# MyRIO_LickometerBreakout_Gamma1a.net
KiCad netlist of a schematic drawn in EAGLE
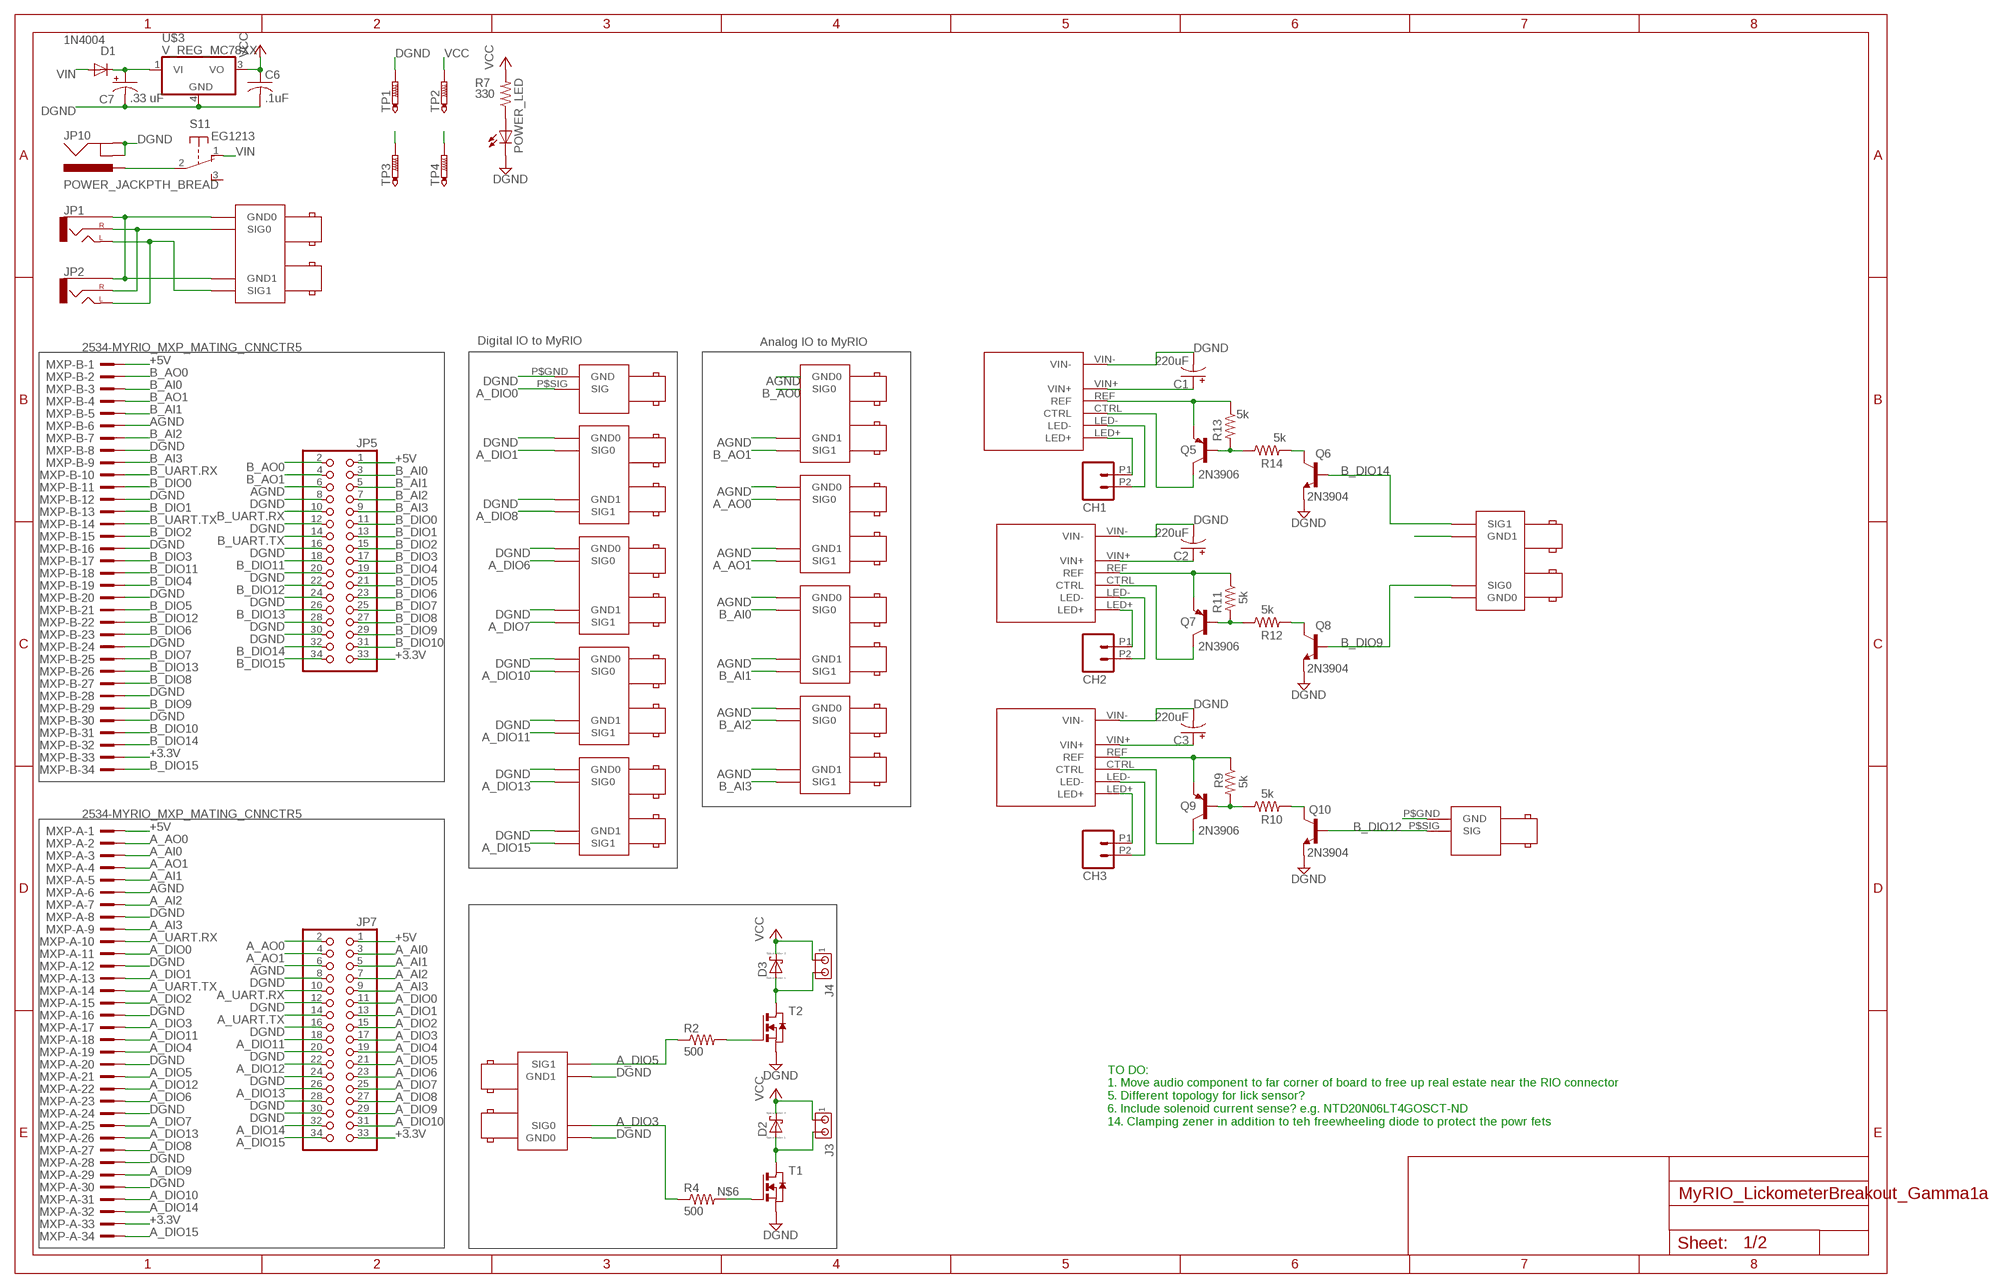
[diagram p0: schematic, sheet 1]
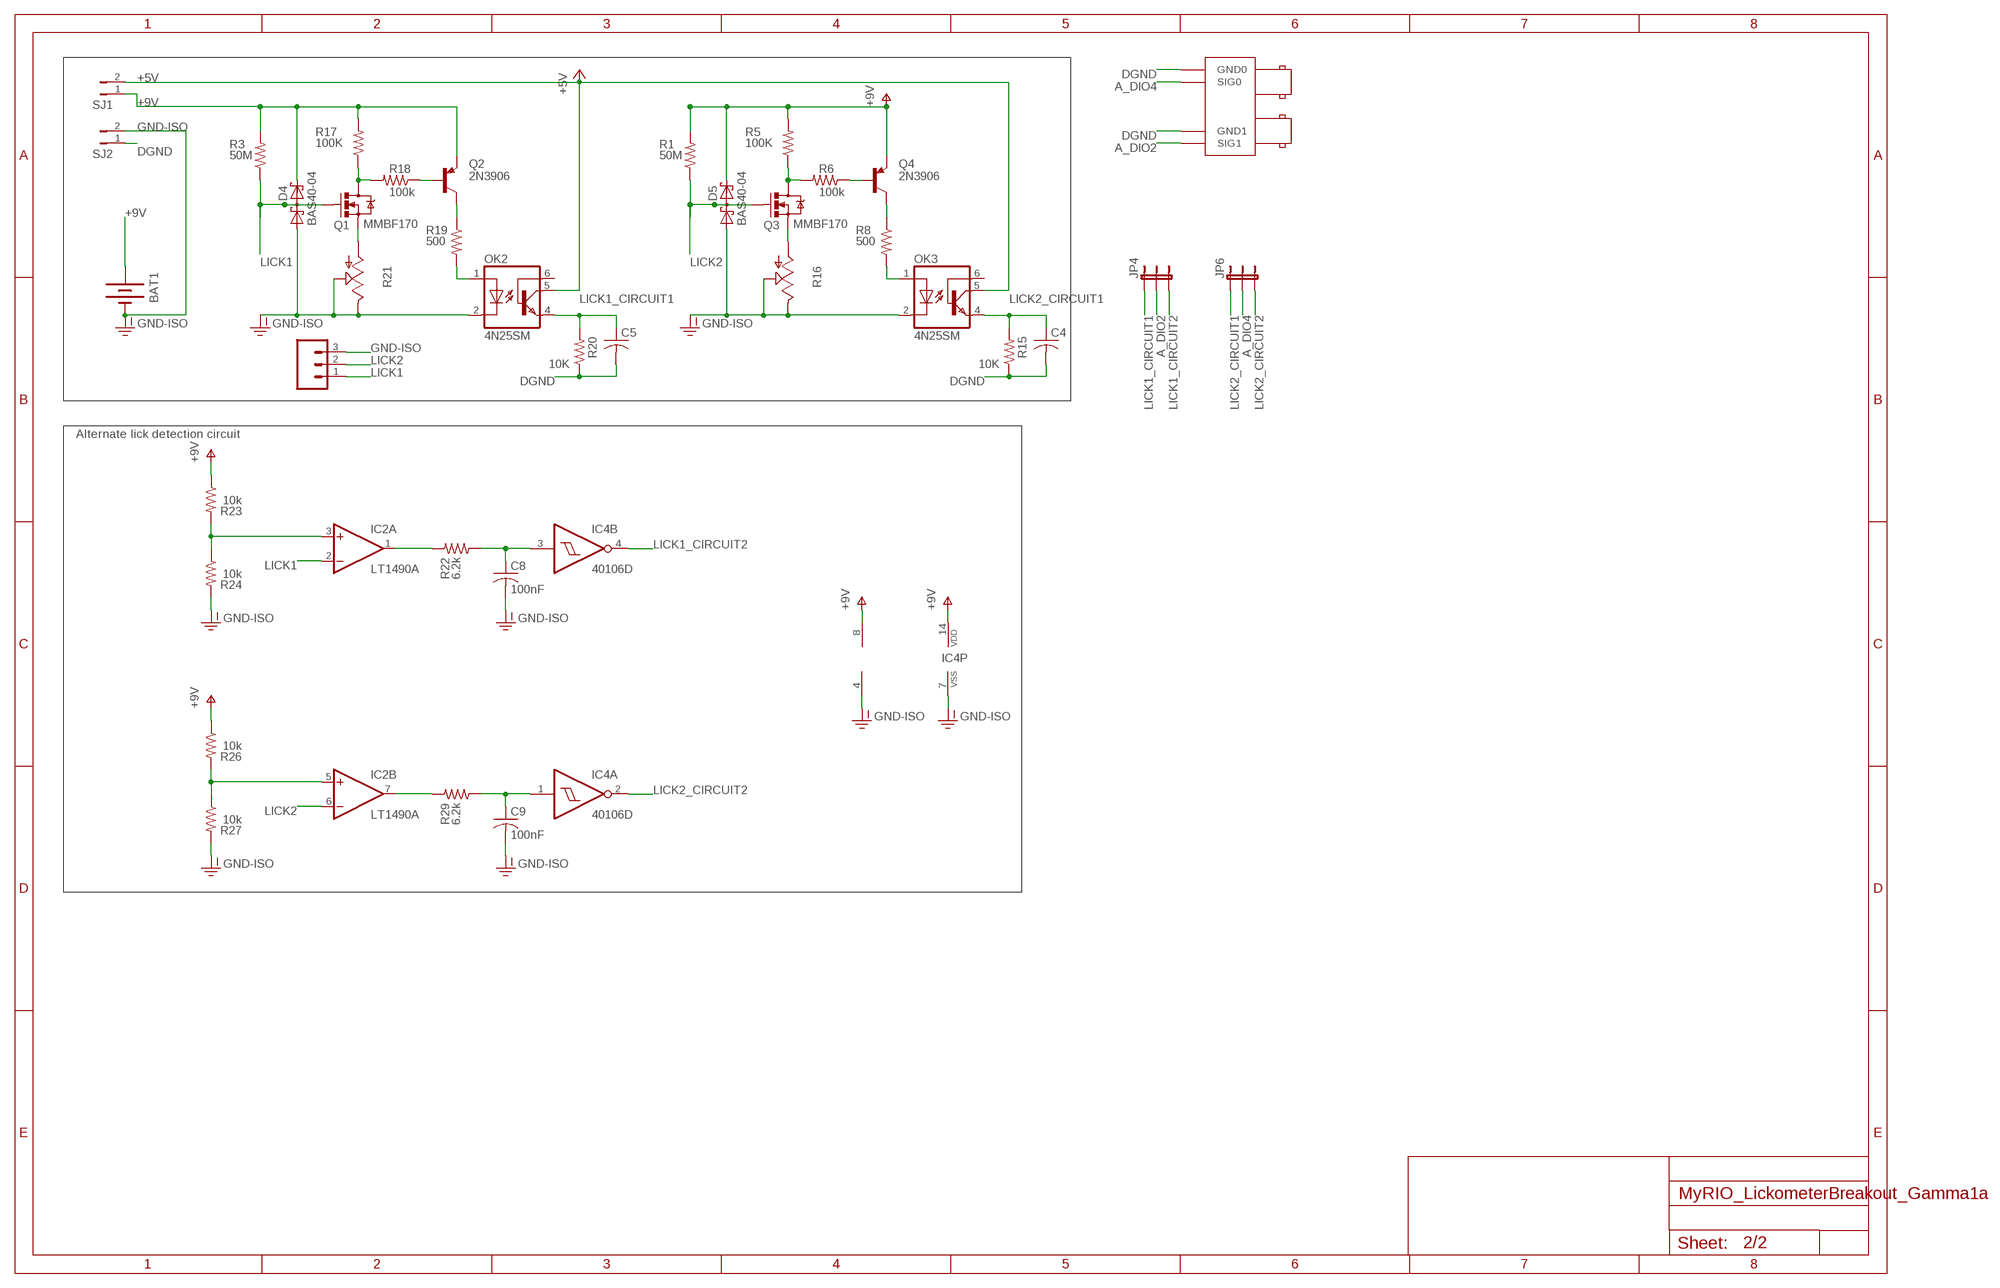
[diagram p1: schematic, sheet 2]

(export (version "E")
  (design (tool "Eeschema 10.0.6"))
  (components
    (comp (ref "BAT1")
      (value "BATTERY9V")
      (footprint "eagle-import:BATTCON_9V")
      (libsource (lib "eagle-import") (part "BATTERY9V"))
    )
    (comp (ref "C4")
      (value "C-US025-024X044")
      (footprint "eagle-import:C025-024X044")
      (libsource (lib "eagle-import") (part "C-US025-024X044"))
    )
    (comp (ref "C5")
      (value "C-US025-024X044")
      (footprint "eagle-import:C025-024X044")
      (libsource (lib "eagle-import") (part "C-US025-024X044"))
    )
    (comp (ref "C8")
      (value "100nF")
      (footprint "eagle-import:C0805")
      (libsource (lib "eagle-import") (part "C-USC0805"))
    )
    (comp (ref "C9")
      (value "100nF")
      (footprint "eagle-import:C0805")
      (libsource (lib "eagle-import") (part "C-USC0805"))
    )
    (comp (ref "D4")
      (value "BAS40-04")
      (footprint "eagle-import:SOT23")
      (libsource (lib "eagle-import") (part "BAS40-04"))
    )
    (comp (ref "D5")
      (value "BAS40-04")
      (footprint "eagle-import:SOT23")
      (libsource (lib "eagle-import") (part "BAS40-04"))
    )
    (comp (ref "IC2")
      (value "LT1490A")
      (footprint "eagle-import:SO08")
      (libsource (lib "eagle-import") (part "LM393D"))
    )
    (comp (ref "IC4")
      (value "40106D")
      (footprint "eagle-import:SO14")
      (libsource (lib "eagle-import") (part "40106D"))
    )
    (comp (ref "JP4")
      (value "JUMPER-3PTH")
      (footprint "eagle-import:1X03")
      (libsource (lib "eagle-import") (part "JUMPER-3PTH"))
    )
    (comp (ref "JP6")
      (value "JUMPER-3PTH")
      (footprint "eagle-import:1X03")
      (libsource (lib "eagle-import") (part "JUMPER-3PTH"))
    )
    (comp (ref "JP11")
      (value "M03POLAR")
      (footprint "eagle-import:MOLEX-1X3")
      (libsource (lib "eagle-import") (part "M03POLAR"))
    )
    (comp (ref "LICK")
      (value "BNC_RIGHT_ANGLE_DOUBLE")
      (footprint "eagle-import:BNC_RIGHT_ANGLE_DOUBLE")
      (libsource (lib "eagle-import") (part "BNC_RIGHT_ANGLE_DOUBLE"))
    )
    (comp (ref "OK2")
      (value "4N25SM")
      (footprint "eagle-import:DIL6-SMD")
      (fields (field (name "MF") "FAIRCHILD SEMICONDUCTOR"))
      (libsource (lib "eagle-import") (part "4N?MS25"))
    )
    (comp (ref "OK3")
      (value "4N25SM")
      (footprint "eagle-import:DIL6-SMD")
      (fields (field (name "MF") "FAIRCHILD SEMICONDUCTOR"))
      (libsource (lib "eagle-import") (part "4N?MS25"))
    )
    (comp (ref "Q1")
      (value "MMBF170")
      (footprint "eagle-import:SOT23-3")
      (libsource (lib "eagle-import") (part "MOSFET-NCHANNELAO3404A"))
    )
    (comp (ref "Q2")
      (value "2N3906")
      (footprint "eagle-import:SOT23-BEC")
      (libsource (lib "eagle-import") (part "-PNP-SOT23-BECMMBT3906LT1"))
    )
    (comp (ref "Q3")
      (value "MMBF170")
      (footprint "eagle-import:SOT23-3")
      (libsource (lib "eagle-import") (part "MOSFET-NCHANNELAO3404A"))
    )
    (comp (ref "Q4")
      (value "2N3906")
      (footprint "eagle-import:SOT23-BEC")
      (libsource (lib "eagle-import") (part "-PNP-SOT23-BECMMBT3906LT1"))
    )
    (comp (ref "R1")
      (value "50M")
      (footprint "eagle-import:0805S")
      (libsource (lib "eagle-import") (part "RESISTOR_SM0805S"))
    )
    (comp (ref "R3")
      (value "50M")
      (footprint "eagle-import:0805S")
      (libsource (lib "eagle-import") (part "RESISTOR_SM0805S"))
    )
    (comp (ref "R5")
      (value "100K")
      (footprint "eagle-import:0805S")
      (libsource (lib "eagle-import") (part "RESISTOR_SM0805S"))
    )
    (comp (ref "R6")
      (value "100k")
      (footprint "eagle-import:0805S")
      (libsource (lib "eagle-import") (part "RESISTOR_SM0805S"))
    )
    (comp (ref "R8")
      (value "500")
      (footprint "eagle-import:0805S")
      (libsource (lib "eagle-import") (part "RESISTOR_SM0805S"))
    )
    (comp (ref "R15")
      (value "10K")
      (footprint "eagle-import:0805S")
      (libsource (lib "eagle-import") (part "RESISTOR_SM0805S"))
    )
    (comp (ref "R16")
      (value "TRIM_US-B25P")
      (footprint "eagle-import:B25P")
      (libsource (lib "eagle-import") (part "TRIM_US-B25P"))
    )
    (comp (ref "R17")
      (value "100K")
      (footprint "eagle-import:0805S")
      (libsource (lib "eagle-import") (part "RESISTOR_SM0805S"))
    )
    (comp (ref "R18")
      (value "100k")
      (footprint "eagle-import:0805S")
      (libsource (lib "eagle-import") (part "RESISTOR_SM0805S"))
    )
    (comp (ref "R19")
      (value "500")
      (footprint "eagle-import:0805S")
      (libsource (lib "eagle-import") (part "RESISTOR_SM0805S"))
    )
    (comp (ref "R20")
      (value "10K")
      (footprint "eagle-import:0805S")
      (libsource (lib "eagle-import") (part "RESISTOR_SM0805S"))
    )
    (comp (ref "R21")
      (value "TRIM_US-B25P")
      (footprint "eagle-import:B25P")
      (libsource (lib "eagle-import") (part "TRIM_US-B25P"))
    )
    (comp (ref "R22")
      (value "6.2k")
      (footprint "eagle-import:0805S")
      (libsource (lib "eagle-import") (part "RESISTOR_SM0805S"))
    )
    (comp (ref "R23")
      (value "10k")
      (footprint "eagle-import:0805S")
      (libsource (lib "eagle-import") (part "RESISTOR_SM0805S"))
    )
    (comp (ref "R24")
      (value "10k")
      (footprint "eagle-import:0805S")
      (libsource (lib "eagle-import") (part "RESISTOR_SM0805S"))
    )
    (comp (ref "R26")
      (value "10k")
      (footprint "eagle-import:0805S")
      (libsource (lib "eagle-import") (part "RESISTOR_SM0805S"))
    )
    (comp (ref "R27")
      (value "10k")
      (footprint "eagle-import:0805S")
      (libsource (lib "eagle-import") (part "RESISTOR_SM0805S"))
    )
    (comp (ref "R29")
      (value "6.2k")
      (footprint "eagle-import:0805S")
      (libsource (lib "eagle-import") (part "RESISTOR_SM0805S"))
    )
    (comp (ref "SJ1")
      (value "JUMPER-PTH-2-NO")
      (footprint "eagle-import:PTH-JUMPER-2-NO_NO_SILK")
      (libsource (lib "eagle-import") (part "JUMPER-PTH-2-NO"))
    )
    (comp (ref "SJ2")
      (value "JUMPER-PTH-2-NO")
      (footprint "eagle-import:PTH-JUMPER-2-NO_NO_SILK")
      (libsource (lib "eagle-import") (part "JUMPER-PTH-2-NO"))
    )
    (comp (ref "AAO_0,1")
      (value "BNC_RIGHT_ANGLE_DOUBLE")
      (footprint "eagle-import:BNC_RIGHT_ANGLE_DOUBLE")
      (libsource (lib "eagle-import") (part "BNC_RIGHT_ANGLE_DOUBLE"))
    )
    (comp (ref "ACTV_REC")
      (value "BNC_RIGHT_ANGLE")
      (footprint "eagle-import:BNC_RIGHT_ANGLE")
      (libsource (lib "eagle-import") (part "BNC_RIGHT_ANGLE"))
    )
    (comp (ref "AUDIO")
      (value "BNC_RIGHT_ANGLE_DOUBLE")
      (footprint "eagle-import:BNC_RIGHT_ANGLE_DOUBLE")
      (libsource (lib "eagle-import") (part "BNC_RIGHT_ANGLE_DOUBLE"))
    )
    (comp (ref "BAI_0,1")
      (value "BNC_RIGHT_ANGLE_DOUBLE")
      (footprint "eagle-import:BNC_RIGHT_ANGLE_DOUBLE")
      (libsource (lib "eagle-import") (part "BNC_RIGHT_ANGLE_DOUBLE"))
    )
    (comp (ref "BAI_2,3")
      (value "BNC_RIGHT_ANGLE_DOUBLE")
      (footprint "eagle-import:BNC_RIGHT_ANGLE_DOUBLE")
      (libsource (lib "eagle-import") (part "BNC_RIGHT_ANGLE_DOUBLE"))
    )
    (comp (ref "BAO_0,1")
      (value "BNC_RIGHT_ANGLE_DOUBLE")
      (footprint "eagle-import:BNC_RIGHT_ANGLE_DOUBLE")
      (libsource (lib "eagle-import") (part "BNC_RIGHT_ANGLE_DOUBLE"))
    )
    (comp (ref "BUCKPUCK1")
      (value "BUCKPUCK-350-I")
      (footprint "eagle-import:BUCKPUCK_I")
      (libsource (lib "eagle-import") (part "BUCKPUCK--?I350"))
    )
    (comp (ref "BUCKPUCK2")
      (value "BUCKPUCK-350-I")
      (footprint "eagle-import:BUCKPUCK_I")
      (libsource (lib "eagle-import") (part "BUCKPUCK--?I350"))
    )
    (comp (ref "BUCKPUCK3")
      (value "BUCKPUCK-350-I")
      (footprint "eagle-import:BUCKPUCK_I")
      (libsource (lib "eagle-import") (part "BUCKPUCK--?I350"))
    )
    (comp (ref "C1")
      (value "220uF")
      (footprint "eagle-import:E5-10,5")
      (libsource (lib "eagle-import") (part "CPOL-USE5-10.5"))
    )
    (comp (ref "C2")
      (value "220uF")
      (footprint "eagle-import:E5-10,5")
      (libsource (lib "eagle-import") (part "CPOL-USE5-10.5"))
    )
    (comp (ref "C3")
      (value "220uF")
      (footprint "eagle-import:E5-10,5")
      (libsource (lib "eagle-import") (part "CPOL-USE5-10.5"))
    )
    (comp (ref "C6")
      (value ".1uF")
      (footprint "eagle-import:C0805")
      (libsource (lib "eagle-import") (part "C-USC0805"))
    )
    (comp (ref "C7")
      (value ".33 uF")
      (footprint "eagle-import:E2,5-5")
      (libsource (lib "eagle-import") (part "CPOL-USE2.5-5"))
    )
    (comp (ref "CAMERA")
      (value "BNC_RIGHT_ANGLE_DOUBLE")
      (footprint "eagle-import:BNC_RIGHT_ANGLE_DOUBLE")
      (libsource (lib "eagle-import") (part "BNC_RIGHT_ANGLE_DOUBLE"))
    )
    (comp (ref "CH1")
      (value "M022.54MM_SCREWTERM")
      (footprint "eagle-import:1X02_2.54_SCREWTERM")
      (libsource (lib "eagle-import") (part "M022.54MM_SCREWTERM"))
    )
    (comp (ref "CH2")
      (value "M022.54MM_SCREWTERM")
      (footprint "eagle-import:1X02_2.54_SCREWTERM")
      (libsource (lib "eagle-import") (part "M022.54MM_SCREWTERM"))
    )
    (comp (ref "CH3")
      (value "M022.54MM_SCREWTERM")
      (footprint "eagle-import:1X02_2.54_SCREWTERM")
      (libsource (lib "eagle-import") (part "M022.54MM_SCREWTERM"))
    )
    (comp (ref "D1")
      (value "1N4004")
      (footprint "eagle-import:DO41-10")
      (libsource (lib "eagle-import") (part "1N4004"))
    )
    (comp (ref "D2")
      (value "SCHOTTKY-DIODE")
      (footprint "eagle-import:DIODE_SMB")
      (libsource (lib "eagle-import") (part "SCHOTTKY-DIODE"))
    )
    (comp (ref "D3")
      (value "SCHOTTKY-DIODE")
      (footprint "eagle-import:DIODE_SMB")
      (libsource (lib "eagle-import") (part "SCHOTTKY-DIODE"))
    )
    (comp (ref "D_FREE1_2")
      (value "BNC_RIGHT_ANGLE_DOUBLE")
      (footprint "eagle-import:BNC_RIGHT_ANGLE_DOUBLE")
      (libsource (lib "eagle-import") (part "BNC_RIGHT_ANGLE_DOUBLE"))
    )
    (comp (ref "D_FREE3_4")
      (value "BNC_RIGHT_ANGLE_DOUBLE")
      (footprint "eagle-import:BNC_RIGHT_ANGLE_DOUBLE")
      (libsource (lib "eagle-import") (part "BNC_RIGHT_ANGLE_DOUBLE"))
    )
    (comp (ref "J3")
      (value "MTA02-100")
      (footprint "eagle-import:10X02MTA")
      (libsource (lib "eagle-import") (part "MTA02-100"))
    )
    (comp (ref "J4")
      (value "MTA02-100")
      (footprint "eagle-import:10X02MTA")
      (libsource (lib "eagle-import") (part "MTA02-100"))
    )
    (comp (ref "JP1")
      (value "AUDIO-JACKPTH")
      (footprint "eagle-import:AUDIO-JACK")
      (libsource (lib "eagle-import") (part "AUDIO-JACKPTH"))
    )
    (comp (ref "JP2")
      (value "AUDIO-JACKPTH")
      (footprint "eagle-import:AUDIO-JACK")
      (libsource (lib "eagle-import") (part "AUDIO-JACKPTH"))
    )
    (comp (ref "JP5")
      (value "PINHD-2X17")
      (footprint "eagle-import:2X17")
      (libsource (lib "eagle-import") (part "PINHD-2X17"))
    )
    (comp (ref "JP7")
      (value "PINHD-2X17")
      (footprint "eagle-import:2X17")
      (libsource (lib "eagle-import") (part "PINHD-2X17"))
    )
    (comp (ref "JP10")
      (value "POWER_JACKPTH_BREAD")
      (footprint "eagle-import:POWER_JACK_PTH_BREAD")
      (libsource (lib "eagle-import") (part "POWER_JACKPTH_BREAD"))
    )
    (comp (ref "LED_CUE")
      (value "BNC_RIGHT_ANGLE")
      (footprint "eagle-import:BNC_RIGHT_ANGLE")
      (libsource (lib "eagle-import") (part "BNC_RIGHT_ANGLE"))
    )
    (comp (ref "LED_MASK")
      (value "BNC_RIGHT_ANGLE_DOUBLE")
      (footprint "eagle-import:BNC_RIGHT_ANGLE_DOUBLE")
      (libsource (lib "eagle-import") (part "BNC_RIGHT_ANGLE_DOUBLE"))
    )
    (comp (ref "MXP-A")
      (value "2534-MYRIO_MXP_MATING_CNNCTR5")
      (footprint "eagle-import:PAK100_2500-5-34-MXP_CONNCTR")
      (libsource (lib "eagle-import") (part "2534-MYRIO_MXP_MATING_CNNCTR5"))
    )
    (comp (ref "MXP-B")
      (value "2534-MYRIO_MXP_MATING_CNNCTR5")
      (footprint "eagle-import:PAK100_2500-5-34-MXP_CONNCTR")
      (libsource (lib "eagle-import") (part "2534-MYRIO_MXP_MATING_CNNCTR5"))
    )
    (comp (ref "POWER_LED")
      (value "LED3MM")
      (footprint "eagle-import:LED3MM")
      (libsource (lib "eagle-import") (part "LED3MM"))
    )
    (comp (ref "Q5")
      (value "2N3906")
      (footprint "eagle-import:SOT23-BEC")
      (libsource (lib "eagle-import") (part "-PNP-SOT23-BECMMBT3906LT1"))
    )
    (comp (ref "Q6")
      (value "2N3904")
      (footprint "eagle-import:SOT23-BEC")
      (libsource (lib "eagle-import") (part "-NPN-SOT23-BECMMBT3904LT1"))
    )
    (comp (ref "Q7")
      (value "2N3906")
      (footprint "eagle-import:SOT23-BEC")
      (libsource (lib "eagle-import") (part "-PNP-SOT23-BECMMBT3906LT1"))
    )
    (comp (ref "Q8")
      (value "2N3904")
      (footprint "eagle-import:SOT23-BEC")
      (libsource (lib "eagle-import") (part "-NPN-SOT23-BECMMBT3904LT1"))
    )
    (comp (ref "Q9")
      (value "2N3906")
      (footprint "eagle-import:SOT23-BEC")
      (libsource (lib "eagle-import") (part "-PNP-SOT23-BECMMBT3906LT1"))
    )
    (comp (ref "Q10")
      (value "2N3904")
      (footprint "eagle-import:SOT23-BEC")
      (libsource (lib "eagle-import") (part "-NPN-SOT23-BECMMBT3904LT1"))
    )
    (comp (ref "R2")
      (value "500")
      (footprint "eagle-import:M1206")
      (libsource (lib "eagle-import") (part "R-US_M1206"))
    )
    (comp (ref "R4")
      (value "500")
      (footprint "eagle-import:M1206")
      (libsource (lib "eagle-import") (part "R-US_M1206"))
    )
    (comp (ref "R7")
      (value "330")
      (footprint "eagle-import:0805S")
      (libsource (lib "eagle-import") (part "RESISTOR_SM0805S"))
    )
    (comp (ref "R9")
      (value "5k")
      (footprint "eagle-import:0805S")
      (libsource (lib "eagle-import") (part "RESISTOR_SM0805S"))
    )
    (comp (ref "R10")
      (value "5k")
      (footprint "eagle-import:0805S")
      (libsource (lib "eagle-import") (part "RESISTOR_SM0805S"))
    )
    (comp (ref "R11")
      (value "5k")
      (footprint "eagle-import:0805S")
      (libsource (lib "eagle-import") (part "RESISTOR_SM0805S"))
    )
    (comp (ref "R12")
      (value "5k")
      (footprint "eagle-import:0805S")
      (libsource (lib "eagle-import") (part "RESISTOR_SM0805S"))
    )
    (comp (ref "R13")
      (value "5k")
      (footprint "eagle-import:0805S")
      (libsource (lib "eagle-import") (part "RESISTOR_SM0805S"))
    )
    (comp (ref "R14")
      (value "5k")
      (footprint "eagle-import:0805S")
      (libsource (lib "eagle-import") (part "RESISTOR_SM0805S"))
    )
    (comp (ref "S1")
      (value "EG1213")
      (footprint "eagle-import:EG1213")
      (libsource (lib "eagle-import") (part "EG1213"))
    )
    (comp (ref "SHUTTER")
      (value "BNC_RIGHT_ANGLE_DOUBLE")
      (footprint "eagle-import:BNC_RIGHT_ANGLE_DOUBLE")
      (libsource (lib "eagle-import") (part "BNC_RIGHT_ANGLE_DOUBLE"))
    )
    (comp (ref "SLN")
      (value "BNC_RIGHT_ANGLE_DOUBLE")
      (footprint "eagle-import:BNC_RIGHT_ANGLE_DOUBLE")
      (libsource (lib "eagle-import") (part "BNC_RIGHT_ANGLE_DOUBLE"))
    )
    (comp (ref "T1")
      (value "NMOSSOT223")
      (footprint "eagle-import:SOT223")
      (libsource (lib "eagle-import") (part "NMOSSOT223"))
    )
    (comp (ref "T2")
      (value "NMOSSOT223")
      (footprint "eagle-import:SOT223")
      (libsource (lib "eagle-import") (part "NMOSSOT223"))
    )
    (comp (ref "TP1")
      (value "PTR1PAD1-17Y")
      (footprint "eagle-import:P1-17Y")
      (libsource (lib "eagle-import") (part "PTR1PAD1-17Y"))
    )
    (comp (ref "TP2")
      (value "PTR1PAD1-17Y")
      (footprint "eagle-import:P1-17Y")
      (libsource (lib "eagle-import") (part "PTR1PAD1-17Y"))
    )
    (comp (ref "TP3")
      (value "PTR1PAD1-17Y")
      (footprint "eagle-import:P1-17Y")
      (libsource (lib "eagle-import") (part "PTR1PAD1-17Y"))
    )
    (comp (ref "TP4")
      (value "PTR1PAD1-17Y")
      (footprint "eagle-import:P1-17Y")
      (libsource (lib "eagle-import") (part "PTR1PAD1-17Y"))
    )
    (comp (ref "U$3")
      (value "V_REG_MC78XX")
      (footprint "eagle-import:DPAK")
      (libsource (lib "eagle-import") (part "V_REG_MC78XX"))
    )
  )
  (nets
    (net (code "1") (name "+3.3V") (class "Default")
      (node (ref "JP5") (pin "33") (pinfunction "33_33") (pintype "passive"))
      (node (ref "JP7") (pin "33") (pinfunction "33_33") (pintype "passive"))
      (node (ref "MXP-A") (pin "33") (pinfunction "KL_33") (pintype "passive"))
      (node (ref "MXP-B") (pin "33") (pinfunction "KL_33") (pintype "passive"))
    )
    (net (code "2") (name "+5V") (class "Default")
      (node (ref "JP5") (pin "1") (pinfunction "1_1") (pintype "passive"))
      (node (ref "JP7") (pin "1") (pinfunction "1_1") (pintype "passive"))
      (node (ref "MXP-A") (pin "1") (pinfunction "KL_1") (pintype "passive"))
      (node (ref "MXP-B") (pin "1") (pinfunction "KL_1") (pintype "passive"))
      (node (ref "OK2") (pin "5") (pinfunction "COL_5") (pintype "passive"))
      (node (ref "OK3") (pin "5") (pinfunction "COL_5") (pintype "passive"))
      (node (ref "SJ1") (pin "2") (pinfunction "2_2") (pintype "passive"))
    )
    (net (code "3") (name "+9V") (class "Default")
      (node (ref "BAT1") (pin "+") (pinfunction "+_+") (pintype "power_in"))
      (node (ref "D4") (pin "2") (pinfunction "C2_2") (pintype "passive"))
      (node (ref "D5") (pin "2") (pinfunction "C2_2") (pintype "passive"))
      (node (ref "IC2") (pin "8") (pinfunction "V+_8") (pintype "power_in"))
      (node (ref "IC4") (pin "14") (pinfunction "VDD_14") (pintype "power_in"))
      (node (ref "Q2") (pin "E") (pinfunction "E_E") (pintype "passive"))
      (node (ref "Q4") (pin "E") (pinfunction "E_E") (pintype "passive"))
      (node (ref "R1") (pin "2") (pinfunction "2_2") (pintype "passive"))
      (node (ref "R17") (pin "2") (pinfunction "2_2") (pintype "passive"))
      (node (ref "R23") (pin "1") (pinfunction "1_1") (pintype "passive"))
      (node (ref "R26") (pin "1") (pinfunction "1_1") (pintype "passive"))
      (node (ref "R3") (pin "2") (pinfunction "2_2") (pintype "passive"))
      (node (ref "R5") (pin "2") (pinfunction "2_2") (pintype "passive"))
      (node (ref "SJ1") (pin "1") (pinfunction "1_1") (pintype "passive"))
      (node (ref "TP4") (pin "TP") (pinfunction "TP_TP") (pintype "input"))
    )
    (net (code "4") (name "AGND") (class "Default")
      (node (ref "AAO_0,1") (pin "P$GND0") (pinfunction "GND0_P$GND0") (pintype "bidirectional"))
      (node (ref "AAO_0,1") (pin "P$GND1") (pinfunction "GND1_P$GND1") (pintype "bidirectional"))
      (node (ref "BAI_0,1") (pin "P$GND0") (pinfunction "GND0_P$GND0") (pintype "bidirectional"))
      (node (ref "BAI_0,1") (pin "P$GND1") (pinfunction "GND1_P$GND1") (pintype "bidirectional"))
      (node (ref "BAI_2,3") (pin "P$GND0") (pinfunction "GND0_P$GND0") (pintype "bidirectional"))
      (node (ref "BAI_2,3") (pin "P$GND1") (pinfunction "GND1_P$GND1") (pintype "bidirectional"))
      (node (ref "BAO_0,1") (pin "P$GND0") (pinfunction "GND0_P$GND0") (pintype "bidirectional"))
      (node (ref "BAO_0,1") (pin "P$GND1") (pinfunction "GND1_P$GND1") (pintype "bidirectional"))
      (node (ref "JP5") (pin "6") (pinfunction "6_6") (pintype "passive"))
      (node (ref "JP7") (pin "6") (pinfunction "6_6") (pintype "passive"))
      (node (ref "MXP-A") (pin "6") (pinfunction "KL_6") (pintype "passive"))
      (node (ref "MXP-B") (pin "6") (pinfunction "KL_6") (pintype "passive"))
    )
    (net (code "5") (name "A_AI0") (class "Default")
      (node (ref "JP7") (pin "3") (pinfunction "3_3") (pintype "passive"))
      (node (ref "MXP-A") (pin "3") (pinfunction "KL_3") (pintype "passive"))
    )
    (net (code "6") (name "A_AI1") (class "Default")
      (node (ref "JP7") (pin "5") (pinfunction "5_5") (pintype "passive"))
      (node (ref "MXP-A") (pin "5") (pinfunction "KL_5") (pintype "passive"))
    )
    (net (code "7") (name "A_AI2") (class "Default")
      (node (ref "JP7") (pin "7") (pinfunction "7_7") (pintype "passive"))
      (node (ref "MXP-A") (pin "7") (pinfunction "KL_7") (pintype "passive"))
    )
    (net (code "8") (name "A_AI3") (class "Default")
      (node (ref "JP7") (pin "9") (pinfunction "9_9") (pintype "passive"))
      (node (ref "MXP-A") (pin "9") (pinfunction "KL_9") (pintype "passive"))
    )
    (net (code "9") (name "A_AO0") (class "Default")
      (node (ref "AAO_0,1") (pin "P$SIG0") (pinfunction "SIG0_P$SIG0") (pintype "bidirectional"))
      (node (ref "JP7") (pin "2") (pinfunction "2_2") (pintype "passive"))
      (node (ref "MXP-A") (pin "2") (pinfunction "KL_2") (pintype "passive"))
    )
    (net (code "10") (name "A_AO1") (class "Default")
      (node (ref "AAO_0,1") (pin "P$SIG1") (pinfunction "SIG1_P$SIG1") (pintype "bidirectional"))
      (node (ref "JP7") (pin "4") (pinfunction "4_4") (pintype "passive"))
      (node (ref "MXP-A") (pin "4") (pinfunction "KL_4") (pintype "passive"))
    )
    (net (code "11") (name "A_DIO0") (class "Default")
      (node (ref "ACTV_REC") (pin "P$SIG") (pinfunction "SIG_P$SIG") (pintype "bidirectional"))
      (node (ref "JP7") (pin "11") (pinfunction "11_11") (pintype "passive"))
      (node (ref "MXP-A") (pin "11") (pinfunction "KL_11") (pintype "passive"))
    )
    (net (code "12") (name "A_DIO1") (class "Default")
      (node (ref "CAMERA") (pin "P$SIG0") (pinfunction "SIG0_P$SIG0") (pintype "bidirectional"))
      (node (ref "JP7") (pin "13") (pinfunction "13_13") (pintype "passive"))
      (node (ref "MXP-A") (pin "13") (pinfunction "KL_13") (pintype "passive"))
    )
    (net (code "13") (name "A_DIO2") (class "Default")
      (node (ref "JP4") (pin "2") (pinfunction "2_2") (pintype "passive"))
      (node (ref "JP7") (pin "15") (pinfunction "15_15") (pintype "passive"))
      (node (ref "LICK") (pin "P$SIG1") (pinfunction "SIG1_P$SIG1") (pintype "bidirectional"))
      (node (ref "MXP-A") (pin "15") (pinfunction "KL_15") (pintype "passive"))
    )
    (net (code "14") (name "A_DIO3") (class "Default")
      (node (ref "JP7") (pin "17") (pinfunction "17_17") (pintype "passive"))
      (node (ref "MXP-A") (pin "17") (pinfunction "KL_17") (pintype "passive"))
      (node (ref "R4") (pin "1") (pinfunction "1_1") (pintype "passive"))
      (node (ref "SLN") (pin "P$SIG0") (pinfunction "SIG0_P$SIG0") (pintype "bidirectional"))
    )
    (net (code "15") (name "A_DIO4") (class "Default")
      (node (ref "JP6") (pin "2") (pinfunction "2_2") (pintype "passive"))
      (node (ref "JP7") (pin "19") (pinfunction "19_19") (pintype "passive"))
      (node (ref "LICK") (pin "P$SIG0") (pinfunction "SIG0_P$SIG0") (pintype "bidirectional"))
      (node (ref "MXP-A") (pin "19") (pinfunction "KL_19") (pintype "passive"))
    )
    (net (code "16") (name "A_DIO5") (class "Default")
      (node (ref "JP7") (pin "21") (pinfunction "21_21") (pintype "passive"))
      (node (ref "MXP-A") (pin "21") (pinfunction "KL_21") (pintype "passive"))
      (node (ref "R2") (pin "1") (pinfunction "1_1") (pintype "passive"))
      (node (ref "SLN") (pin "P$SIG1") (pinfunction "SIG1_P$SIG1") (pintype "bidirectional"))
    )
    (net (code "17") (name "A_DIO6") (class "Default")
      (node (ref "JP7") (pin "23") (pinfunction "23_23") (pintype "passive"))
      (node (ref "MXP-A") (pin "23") (pinfunction "KL_23") (pintype "passive"))
      (node (ref "SHUTTER") (pin "P$SIG0") (pinfunction "SIG0_P$SIG0") (pintype "bidirectional"))
    )
    (net (code "18") (name "A_DIO7") (class "Default")
      (node (ref "JP7") (pin "25") (pinfunction "25_25") (pintype "passive"))
      (node (ref "MXP-A") (pin "25") (pinfunction "KL_25") (pintype "passive"))
      (node (ref "SHUTTER") (pin "P$SIG1") (pinfunction "SIG1_P$SIG1") (pintype "bidirectional"))
    )
    (net (code "19") (name "A_DIO8") (class "Default")
      (node (ref "CAMERA") (pin "P$SIG1") (pinfunction "SIG1_P$SIG1") (pintype "bidirectional"))
      (node (ref "JP7") (pin "27") (pinfunction "27_27") (pintype "passive"))
      (node (ref "MXP-A") (pin "27") (pinfunction "KL_27") (pintype "passive"))
    )
    (net (code "20") (name "A_DIO9") (class "Default")
      (node (ref "JP7") (pin "29") (pinfunction "29_29") (pintype "passive"))
      (node (ref "MXP-A") (pin "29") (pinfunction "KL_29") (pintype "passive"))
    )
    (net (code "21") (name "A_DIO10") (class "Default")
      (node (ref "D_FREE1_2") (pin "P$SIG0") (pinfunction "SIG0_P$SIG0") (pintype "bidirectional"))
      (node (ref "JP7") (pin "31") (pinfunction "31_31") (pintype "passive"))
      (node (ref "MXP-A") (pin "31") (pinfunction "KL_31") (pintype "passive"))
    )
    (net (code "22") (name "A_DIO11") (class "Default")
      (node (ref "D_FREE1_2") (pin "P$SIG1") (pinfunction "SIG1_P$SIG1") (pintype "bidirectional"))
      (node (ref "JP7") (pin "18") (pinfunction "18_18") (pintype "passive"))
      (node (ref "MXP-A") (pin "18") (pinfunction "KL_18") (pintype "passive"))
    )
    (net (code "23") (name "A_DIO12") (class "Default")
      (node (ref "JP7") (pin "22") (pinfunction "22_22") (pintype "passive"))
      (node (ref "MXP-A") (pin "22") (pinfunction "KL_22") (pintype "passive"))
    )
    (net (code "24") (name "A_DIO13") (class "Default")
      (node (ref "D_FREE3_4") (pin "P$SIG0") (pinfunction "SIG0_P$SIG0") (pintype "bidirectional"))
      (node (ref "JP7") (pin "26") (pinfunction "26_26") (pintype "passive"))
      (node (ref "MXP-A") (pin "26") (pinfunction "KL_26") (pintype "passive"))
    )
    (net (code "25") (name "A_DIO14") (class "Default")
      (node (ref "JP7") (pin "32") (pinfunction "32_32") (pintype "passive"))
      (node (ref "MXP-A") (pin "32") (pinfunction "KL_32") (pintype "passive"))
    )
    (net (code "26") (name "A_DIO15") (class "Default")
      (node (ref "D_FREE3_4") (pin "P$SIG1") (pinfunction "SIG1_P$SIG1") (pintype "bidirectional"))
      (node (ref "JP7") (pin "34") (pinfunction "34_34") (pintype "passive"))
      (node (ref "MXP-A") (pin "34") (pinfunction "KL_34") (pintype "passive"))
    )
    (net (code "27") (name "A_UART.RX") (class "Default")
      (node (ref "JP7") (pin "10") (pinfunction "10_10") (pintype "passive"))
      (node (ref "MXP-A") (pin "10") (pinfunction "KL_10") (pintype "passive"))
    )
    (net (code "28") (name "A_UART.TX") (class "Default")
      (node (ref "JP7") (pin "14") (pinfunction "14_14") (pintype "passive"))
      (node (ref "MXP-A") (pin "14") (pinfunction "KL_14") (pintype "passive"))
    )
    (net (code "29") (name "B_AI0") (class "Default")
      (node (ref "BAI_0,1") (pin "P$SIG0") (pinfunction "SIG0_P$SIG0") (pintype "bidirectional"))
      (node (ref "JP5") (pin "3") (pinfunction "3_3") (pintype "passive"))
      (node (ref "MXP-B") (pin "3") (pinfunction "KL_3") (pintype "passive"))
    )
    (net (code "30") (name "B_AI1") (class "Default")
      (node (ref "BAI_0,1") (pin "P$SIG1") (pinfunction "SIG1_P$SIG1") (pintype "bidirectional"))
      (node (ref "JP5") (pin "5") (pinfunction "5_5") (pintype "passive"))
      (node (ref "MXP-B") (pin "5") (pinfunction "KL_5") (pintype "passive"))
    )
    (net (code "31") (name "B_AI2") (class "Default")
      (node (ref "BAI_2,3") (pin "P$SIG0") (pinfunction "SIG0_P$SIG0") (pintype "bidirectional"))
      (node (ref "JP5") (pin "7") (pinfunction "7_7") (pintype "passive"))
      (node (ref "MXP-B") (pin "7") (pinfunction "KL_7") (pintype "passive"))
    )
    (net (code "32") (name "B_AI3") (class "Default")
      (node (ref "BAI_2,3") (pin "P$SIG1") (pinfunction "SIG1_P$SIG1") (pintype "bidirectional"))
      (node (ref "JP5") (pin "9") (pinfunction "9_9") (pintype "passive"))
      (node (ref "MXP-B") (pin "9") (pinfunction "KL_9") (pintype "passive"))
    )
    (net (code "33") (name "B_AO0") (class "Default")
      (node (ref "BAO_0,1") (pin "P$SIG0") (pinfunction "SIG0_P$SIG0") (pintype "bidirectional"))
      (node (ref "JP5") (pin "2") (pinfunction "2_2") (pintype "passive"))
      (node (ref "MXP-B") (pin "2") (pinfunction "KL_2") (pintype "passive"))
    )
    (net (code "34") (name "B_AO1") (class "Default")
      (node (ref "BAO_0,1") (pin "P$SIG1") (pinfunction "SIG1_P$SIG1") (pintype "bidirectional"))
      (node (ref "JP5") (pin "4") (pinfunction "4_4") (pintype "passive"))
      (node (ref "MXP-B") (pin "4") (pinfunction "KL_4") (pintype "passive"))
    )
    (net (code "35") (name "B_DIO0") (class "Default")
      (node (ref "JP5") (pin "11") (pinfunction "11_11") (pintype "passive"))
      (node (ref "MXP-B") (pin "11") (pinfunction "KL_11") (pintype "passive"))
    )
    (net (code "36") (name "B_DIO1") (class "Default")
      (node (ref "JP5") (pin "13") (pinfunction "13_13") (pintype "passive"))
      (node (ref "MXP-B") (pin "13") (pinfunction "KL_13") (pintype "passive"))
    )
    (net (code "37") (name "B_DIO2") (class "Default")
      (node (ref "JP5") (pin "15") (pinfunction "15_15") (pintype "passive"))
      (node (ref "MXP-B") (pin "15") (pinfunction "KL_15") (pintype "passive"))
    )
    (net (code "38") (name "B_DIO3") (class "Default")
      (node (ref "JP5") (pin "17") (pinfunction "17_17") (pintype "passive"))
      (node (ref "MXP-B") (pin "17") (pinfunction "KL_17") (pintype "passive"))
    )
    (net (code "39") (name "B_DIO4") (class "Default")
      (node (ref "JP5") (pin "19") (pinfunction "19_19") (pintype "passive"))
      (node (ref "MXP-B") (pin "19") (pinfunction "KL_19") (pintype "passive"))
    )
    (net (code "40") (name "B_DIO5") (class "Default")
      (node (ref "JP5") (pin "21") (pinfunction "21_21") (pintype "passive"))
      (node (ref "MXP-B") (pin "21") (pinfunction "KL_21") (pintype "passive"))
    )
    (net (code "41") (name "B_DIO6") (class "Default")
      (node (ref "JP5") (pin "23") (pinfunction "23_23") (pintype "passive"))
      (node (ref "MXP-B") (pin "23") (pinfunction "KL_23") (pintype "passive"))
    )
    (net (code "42") (name "B_DIO7") (class "Default")
      (node (ref "JP5") (pin "25") (pinfunction "25_25") (pintype "passive"))
      (node (ref "MXP-B") (pin "25") (pinfunction "KL_25") (pintype "passive"))
    )
    (net (code "43") (name "B_DIO8") (class "Default")
      (node (ref "JP5") (pin "27") (pinfunction "27_27") (pintype "passive"))
      (node (ref "MXP-B") (pin "27") (pinfunction "KL_27") (pintype "passive"))
    )
    (net (code "44") (name "B_DIO9") (class "Default")
      (node (ref "JP5") (pin "29") (pinfunction "29_29") (pintype "passive"))
      (node (ref "LED_MASK") (pin "P$SIG0") (pinfunction "SIG0_P$SIG0") (pintype "bidirectional"))
      (node (ref "MXP-B") (pin "29") (pinfunction "KL_29") (pintype "passive"))
      (node (ref "Q8") (pin "B") (pinfunction "B_B") (pintype "passive"))
    )
    (net (code "45") (name "B_DIO10") (class "Default")
      (node (ref "JP5") (pin "31") (pinfunction "31_31") (pintype "passive"))
      (node (ref "MXP-B") (pin "31") (pinfunction "KL_31") (pintype "passive"))
    )
    (net (code "46") (name "B_DIO11") (class "Default")
      (node (ref "JP5") (pin "18") (pinfunction "18_18") (pintype "passive"))
      (node (ref "MXP-B") (pin "18") (pinfunction "KL_18") (pintype "passive"))
    )
    (net (code "47") (name "B_DIO12") (class "Default")
      (node (ref "JP5") (pin "22") (pinfunction "22_22") (pintype "passive"))
      (node (ref "LED_CUE") (pin "P$SIG") (pinfunction "SIG_P$SIG") (pintype "bidirectional"))
      (node (ref "MXP-B") (pin "22") (pinfunction "KL_22") (pintype "passive"))
      (node (ref "Q10") (pin "B") (pinfunction "B_B") (pintype "passive"))
    )
    (net (code "48") (name "B_DIO13") (class "Default")
      (node (ref "JP5") (pin "26") (pinfunction "26_26") (pintype "passive"))
      (node (ref "MXP-B") (pin "26") (pinfunction "KL_26") (pintype "passive"))
    )
    (net (code "49") (name "B_DIO14") (class "Default")
      (node (ref "JP5") (pin "32") (pinfunction "32_32") (pintype "passive"))
      (node (ref "LED_MASK") (pin "P$SIG1") (pinfunction "SIG1_P$SIG1") (pintype "bidirectional"))
      (node (ref "MXP-B") (pin "32") (pinfunction "KL_32") (pintype "passive"))
      (node (ref "Q6") (pin "B") (pinfunction "B_B") (pintype "passive"))
    )
    (net (code "50") (name "B_DIO15") (class "Default")
      (node (ref "JP5") (pin "34") (pinfunction "34_34") (pintype "passive"))
      (node (ref "MXP-B") (pin "34") (pinfunction "KL_34") (pintype "passive"))
    )
    (net (code "51") (name "B_UART.RX") (class "Default")
      (node (ref "JP5") (pin "10") (pinfunction "10_10") (pintype "passive"))
      (node (ref "MXP-B") (pin "10") (pinfunction "KL_10") (pintype "passive"))
    )
    (net (code "52") (name "B_UART.TX") (class "Default")
      (node (ref "JP5") (pin "14") (pinfunction "14_14") (pintype "passive"))
      (node (ref "MXP-B") (pin "14") (pinfunction "KL_14") (pintype "passive"))
    )
    (net (code "53") (name "DGND") (class "Default")
      (node (ref "ACTV_REC") (pin "P$GND") (pinfunction "GND_P$GND") (pintype "bidirectional"))
      (node (ref "BUCKPUCK1") (pin "LED-") (pinfunction "LED-_LED-") (pintype "bidirectional"))
      (node (ref "BUCKPUCK1") (pin "VIN-") (pinfunction "VIN-_VIN-") (pintype "bidirectional"))
      (node (ref "BUCKPUCK2") (pin "LED-") (pinfunction "LED-_LED-") (pintype "bidirectional"))
      (node (ref "BUCKPUCK2") (pin "VIN-") (pinfunction "VIN-_VIN-") (pintype "bidirectional"))
      (node (ref "BUCKPUCK3") (pin "LED-") (pinfunction "LED-_LED-") (pintype "bidirectional"))
      (node (ref "BUCKPUCK3") (pin "VIN-") (pinfunction "VIN-_VIN-") (pintype "bidirectional"))
      (node (ref "C1") (pin "-") (pinfunction "-_-") (pintype "passive"))
      (node (ref "C2") (pin "-") (pinfunction "-_-") (pintype "passive"))
      (node (ref "C3") (pin "-") (pinfunction "-_-") (pintype "passive"))
      (node (ref "C4") (pin "2") (pinfunction "2_2") (pintype "passive"))
      (node (ref "C5") (pin "2") (pinfunction "2_2") (pintype "passive"))
      (node (ref "C6") (pin "2") (pinfunction "2_2") (pintype "passive"))
      (node (ref "C7") (pin "-") (pinfunction "-_-") (pintype "passive"))
      (node (ref "CAMERA") (pin "P$GND0") (pinfunction "GND0_P$GND0") (pintype "bidirectional"))
      (node (ref "CAMERA") (pin "P$GND1") (pinfunction "GND1_P$GND1") (pintype "bidirectional"))
      (node (ref "CH1") (pin "P2") (pinfunction "2_P2") (pintype "passive"))
      (node (ref "CH2") (pin "P2") (pinfunction "2_P2") (pintype "passive"))
      (node (ref "CH3") (pin "P2") (pinfunction "2_P2") (pintype "passive"))
      (node (ref "D_FREE1_2") (pin "P$GND0") (pinfunction "GND0_P$GND0") (pintype "bidirectional"))
      (node (ref "D_FREE1_2") (pin "P$GND1") (pinfunction "GND1_P$GND1") (pintype "bidirectional"))
      (node (ref "D_FREE3_4") (pin "P$GND0") (pinfunction "GND0_P$GND0") (pintype "bidirectional"))
      (node (ref "D_FREE3_4") (pin "P$GND1") (pinfunction "GND1_P$GND1") (pintype "bidirectional"))
      (node (ref "JP10") (pin "GND") (pinfunction "GND_GND") (pintype "bidirectional"))
      (node (ref "JP10") (pin "GNDBREAK") (pinfunction "GNDBREAK_GNDBREAK") (pintype "bidirectional"))
      (node (ref "JP5") (pin "12") (pinfunction "12_12") (pintype "passive"))
      (node (ref "JP5") (pin "16") (pinfunction "16_16") (pintype "passive"))
      (node (ref "JP5") (pin "20") (pinfunction "20_20") (pintype "passive"))
      (node (ref "JP5") (pin "24") (pinfunction "24_24") (pintype "passive"))
      (node (ref "JP5") (pin "28") (pinfunction "28_28") (pintype "passive"))
      (node (ref "JP5") (pin "30") (pinfunction "30_30") (pintype "passive"))
      (node (ref "JP5") (pin "8") (pinfunction "8_8") (pintype "passive"))
      (node (ref "JP7") (pin "12") (pinfunction "12_12") (pintype "passive"))
      (node (ref "JP7") (pin "16") (pinfunction "16_16") (pintype "passive"))
      (node (ref "JP7") (pin "20") (pinfunction "20_20") (pintype "passive"))
      (node (ref "JP7") (pin "24") (pinfunction "24_24") (pintype "passive"))
      (node (ref "JP7") (pin "28") (pinfunction "28_28") (pintype "passive"))
      (node (ref "JP7") (pin "30") (pinfunction "30_30") (pintype "passive"))
      (node (ref "JP7") (pin "8") (pinfunction "8_8") (pintype "passive"))
      (node (ref "LED_CUE") (pin "P$GND") (pinfunction "GND_P$GND") (pintype "bidirectional"))
      (node (ref "LED_MASK") (pin "P$GND0") (pinfunction "GND0_P$GND0") (pintype "bidirectional"))
      (node (ref "LED_MASK") (pin "P$GND1") (pinfunction "GND1_P$GND1") (pintype "bidirectional"))
      (node (ref "LICK") (pin "P$GND0") (pinfunction "GND0_P$GND0") (pintype "bidirectional"))
      (node (ref "LICK") (pin "P$GND1") (pinfunction "GND1_P$GND1") (pintype "bidirectional"))
      (node (ref "MXP-A") (pin "12") (pinfunction "KL_12") (pintype "passive"))
      (node (ref "MXP-A") (pin "16") (pinfunction "KL_16") (pintype "passive"))
      (node (ref "MXP-A") (pin "20") (pinfunction "KL_20") (pintype "passive"))
      (node (ref "MXP-A") (pin "24") (pinfunction "KL_24") (pintype "passive"))
      (node (ref "MXP-A") (pin "28") (pinfunction "KL_28") (pintype "passive"))
      (node (ref "MXP-A") (pin "30") (pinfunction "KL_30") (pintype "passive"))
      (node (ref "MXP-A") (pin "8") (pinfunction "KL_8") (pintype "passive"))
      (node (ref "MXP-B") (pin "12") (pinfunction "KL_12") (pintype "passive"))
      (node (ref "MXP-B") (pin "16") (pinfunction "KL_16") (pintype "passive"))
      (node (ref "MXP-B") (pin "20") (pinfunction "KL_20") (pintype "passive"))
      (node (ref "MXP-B") (pin "24") (pinfunction "KL_24") (pintype "passive"))
      (node (ref "MXP-B") (pin "28") (pinfunction "KL_28") (pintype "passive"))
      (node (ref "MXP-B") (pin "30") (pinfunction "KL_30") (pintype "passive"))
      (node (ref "MXP-B") (pin "8") (pinfunction "KL_8") (pintype "passive"))
      (node (ref "POWER_LED") (pin "K") (pinfunction "C_K") (pintype "passive"))
      (node (ref "Q10") (pin "E") (pinfunction "E_E") (pintype "passive"))
      (node (ref "Q6") (pin "E") (pinfunction "E_E") (pintype "passive"))
      (node (ref "Q8") (pin "E") (pinfunction "E_E") (pintype "passive"))
      (node (ref "R15") (pin "1") (pinfunction "1_1") (pintype "passive"))
      (node (ref "R20") (pin "1") (pinfunction "1_1") (pintype "passive"))
      (node (ref "SHUTTER") (pin "P$GND0") (pinfunction "GND0_P$GND0") (pintype "bidirectional"))
      (node (ref "SHUTTER") (pin "P$GND1") (pinfunction "GND1_P$GND1") (pintype "bidirectional"))
      (node (ref "SJ2") (pin "1") (pinfunction "1_1") (pintype "passive"))
      (node (ref "SLN") (pin "P$GND0") (pinfunction "GND0_P$GND0") (pintype "bidirectional"))
      (node (ref "SLN") (pin "P$GND1") (pinfunction "GND1_P$GND1") (pintype "bidirectional"))
      (node (ref "T1") (pin "3") (pinfunction "S_3") (pintype "passive"))
      (node (ref "T2") (pin "3") (pinfunction "S_3") (pintype "passive"))
      (node (ref "TP1") (pin "TP") (pinfunction "TP_TP") (pintype "input"))
      (node (ref "U$3") (pin "4") (pinfunction "GND_4") (pintype "passive"))
    )
    (net (code "54") (name "GND-ISO") (class "Default")
      (node (ref "BAT1") (pin "-") (pinfunction "-_-") (pintype "power_in"))
      (node (ref "C8") (pin "2") (pinfunction "2_2") (pintype "passive"))
      (node (ref "C9") (pin "2") (pinfunction "2_2") (pintype "passive"))
      (node (ref "D4") (pin "1") (pinfunction "A1_1") (pintype "passive"))
      (node (ref "D5") (pin "1") (pinfunction "A1_1") (pintype "passive"))
      (node (ref "IC2") (pin "4") (pinfunction "V-_4") (pintype "power_in"))
      (node (ref "IC4") (pin "7") (pinfunction "VSS_7") (pintype "power_in"))
      (node (ref "JP11") (pin "3") (pinfunction "3_3") (pintype "passive"))
      (node (ref "OK2") (pin "2") (pinfunction "C_2") (pintype "passive"))
      (node (ref "OK3") (pin "2") (pinfunction "C_2") (pintype "passive"))
      (node (ref "R16") (pin "E") (pinfunction "E_E") (pintype "passive"))
      (node (ref "R16") (pin "S") (pinfunction "S_S") (pintype "passive"))
      (node (ref "R21") (pin "E") (pinfunction "E_E") (pintype "passive"))
      (node (ref "R21") (pin "S") (pinfunction "S_S") (pintype "passive"))
      (node (ref "R24") (pin "2") (pinfunction "2_2") (pintype "passive"))
      (node (ref "R27") (pin "2") (pinfunction "2_2") (pintype "passive"))
      (node (ref "SJ2") (pin "2") (pinfunction "2_2") (pintype "passive"))
      (node (ref "TP3") (pin "TP") (pinfunction "TP_TP") (pintype "input"))
    )
    (net (code "55") (name "LICK1") (class "Default")
      (node (ref "D4") (pin "3") (pinfunction "C1A2_3") (pintype "passive"))
      (node (ref "IC2") (pin "2") (pinfunction "-IN_2") (pintype "input"))
      (node (ref "JP11") (pin "1") (pinfunction "1_1") (pintype "passive"))
      (node (ref "Q1") (pin "1") (pinfunction "G_1") (pintype "passive"))
      (node (ref "R3") (pin "1") (pinfunction "1_1") (pintype "passive"))
    )
    (net (code "56") (name "LICK1_CIRCUIT1") (class "Default")
      (node (ref "C5") (pin "1") (pinfunction "1_1") (pintype "passive"))
      (node (ref "JP4") (pin "1") (pinfunction "1_1") (pintype "passive"))
      (node (ref "OK2") (pin "4") (pinfunction "EMI_4") (pintype "passive"))
      (node (ref "R20") (pin "2") (pinfunction "2_2") (pintype "passive"))
    )
    (net (code "57") (name "LICK1_CIRCUIT2") (class "Default")
      (node (ref "IC4") (pin "4") (pinfunction "O_4") (pintype "output"))
      (node (ref "JP4") (pin "3") (pinfunction "3_3") (pintype "passive"))
    )
    (net (code "58") (name "LICK2") (class "Default")
      (node (ref "D5") (pin "3") (pinfunction "C1A2_3") (pintype "passive"))
      (node (ref "IC2") (pin "6") (pinfunction "-IN_6") (pintype "input"))
      (node (ref "JP11") (pin "2") (pinfunction "2_2") (pintype "passive"))
      (node (ref "Q3") (pin "1") (pinfunction "G_1") (pintype "passive"))
      (node (ref "R1") (pin "1") (pinfunction "1_1") (pintype "passive"))
    )
    (net (code "59") (name "LICK2_CIRCUIT1") (class "Default")
      (node (ref "C4") (pin "1") (pinfunction "1_1") (pintype "passive"))
      (node (ref "JP6") (pin "1") (pinfunction "1_1") (pintype "passive"))
      (node (ref "OK3") (pin "4") (pinfunction "EMI_4") (pintype "passive"))
      (node (ref "R15") (pin "2") (pinfunction "2_2") (pintype "passive"))
    )
    (net (code "60") (name "LICK2_CIRCUIT2") (class "Default")
      (node (ref "IC4") (pin "2") (pinfunction "O_2") (pintype "output"))
      (node (ref "JP6") (pin "3") (pinfunction "3_3") (pintype "passive"))
    )
    (net (code "61") (name "N$6") (class "Default")
      (node (ref "R4") (pin "2") (pinfunction "2_2") (pintype "passive"))
      (node (ref "T1") (pin "1") (pinfunction "G_1") (pintype "passive"))
    )
    (net (code "62") (name "N$16") (class "Default")
      (node (ref "BUCKPUCK1") (pin "VIN+") (pinfunction "VIN+_VIN+") (pintype "bidirectional"))
      (node (ref "BUCKPUCK2") (pin "VIN+") (pinfunction "VIN+_VIN+") (pintype "bidirectional"))
      (node (ref "BUCKPUCK3") (pin "VIN+") (pinfunction "VIN+_VIN+") (pintype "bidirectional"))
      (node (ref "C1") (pin "+") (pinfunction "+_+") (pintype "passive"))
      (node (ref "C2") (pin "+") (pinfunction "+_+") (pintype "passive"))
      (node (ref "C3") (pin "+") (pinfunction "+_+") (pintype "passive"))
      (node (ref "C7") (pin "+") (pinfunction "+_+") (pintype "passive"))
      (node (ref "D1") (pin "C") (pinfunction "C_C") (pintype "passive"))
      (node (ref "U$3") (pin "1") (pinfunction "VI_1") (pintype "input"))
    )
    (net (code "63") (name "Net-(AUDIO-GND0)") (class "Default")
      (node (ref "AUDIO") (pin "P$GND0") (pinfunction "GND0_P$GND0") (pintype "bidirectional"))
      (node (ref "AUDIO") (pin "P$GND1") (pinfunction "GND1_P$GND1") (pintype "bidirectional"))
      (node (ref "JP1") (pin "SLEEVE") (pinfunction "SLEEVE_SLEEVE") (pintype "bidirectional"))
      (node (ref "JP2") (pin "SLEEVE") (pinfunction "SLEEVE_SLEEVE") (pintype "bidirectional"))
    )
    (net (code "64") (name "Net-(AUDIO-SIG0)") (class "Default")
      (node (ref "AUDIO") (pin "P$SIG0") (pinfunction "SIG0_P$SIG0") (pintype "bidirectional"))
      (node (ref "JP1") (pin "RING") (pinfunction "RIGHT_RING") (pintype "bidirectional"))
      (node (ref "JP2") (pin "RING") (pinfunction "RIGHT_RING") (pintype "bidirectional"))
    )
    (net (code "65") (name "Net-(AUDIO-SIG1)") (class "Default")
      (node (ref "AUDIO") (pin "P$SIG1") (pinfunction "SIG1_P$SIG1") (pintype "bidirectional"))
      (node (ref "JP1") (pin "TIP") (pinfunction "LEFT_TIP") (pintype "bidirectional"))
      (node (ref "JP2") (pin "TIP") (pinfunction "LEFT_TIP") (pintype "bidirectional"))
    )
    (net (code "66") (name "Net-(BUCKPUCK1-PadCTRL)") (class "Default")
      (node (ref "BUCKPUCK1") (pin "CTRL") (pinfunction "CTRL_CTRL") (pintype "bidirectional"))
      (node (ref "Q5") (pin "C") (pinfunction "C_C") (pintype "passive"))
    )
    (net (code "67") (name "Net-(BUCKPUCK1-PadREF)") (class "Default")
      (node (ref "BUCKPUCK1") (pin "REF") (pinfunction "REF_REF") (pintype "bidirectional"))
      (node (ref "Q5") (pin "E") (pinfunction "E_E") (pintype "passive"))
      (node (ref "R13") (pin "1") (pinfunction "1_1") (pintype "passive"))
    )
    (net (code "68") (name "Net-(BUCKPUCK2-PadCTRL)") (class "Default")
      (node (ref "BUCKPUCK2") (pin "CTRL") (pinfunction "CTRL_CTRL") (pintype "bidirectional"))
      (node (ref "Q7") (pin "C") (pinfunction "C_C") (pintype "passive"))
    )
    (net (code "69") (name "Net-(BUCKPUCK2-PadREF)") (class "Default")
      (node (ref "BUCKPUCK2") (pin "REF") (pinfunction "REF_REF") (pintype "bidirectional"))
      (node (ref "Q7") (pin "E") (pinfunction "E_E") (pintype "passive"))
      (node (ref "R11") (pin "1") (pinfunction "1_1") (pintype "passive"))
    )
    (net (code "70") (name "Net-(BUCKPUCK3-PadCTRL)") (class "Default")
      (node (ref "BUCKPUCK3") (pin "CTRL") (pinfunction "CTRL_CTRL") (pintype "bidirectional"))
      (node (ref "Q9") (pin "C") (pinfunction "C_C") (pintype "passive"))
    )
    (net (code "71") (name "Net-(BUCKPUCK3-PadREF)") (class "Default")
      (node (ref "BUCKPUCK3") (pin "REF") (pinfunction "REF_REF") (pintype "bidirectional"))
      (node (ref "Q9") (pin "E") (pinfunction "E_E") (pintype "passive"))
      (node (ref "R9") (pin "1") (pinfunction "1_1") (pintype "passive"))
    )
    (net (code "72") (name "Net-(CH1-1)") (class "Default")
      (node (ref "BUCKPUCK1") (pin "LED+") (pinfunction "LED+_LED+") (pintype "bidirectional"))
      (node (ref "CH1") (pin "P1") (pinfunction "1_P1") (pintype "passive"))
    )
    (net (code "73") (name "Net-(CH2-1)") (class "Default")
      (node (ref "BUCKPUCK2") (pin "LED+") (pinfunction "LED+_LED+") (pintype "bidirectional"))
      (node (ref "CH2") (pin "P1") (pinfunction "1_P1") (pintype "passive"))
    )
    (net (code "74") (name "Net-(CH3-1)") (class "Default")
      (node (ref "BUCKPUCK3") (pin "LED+") (pinfunction "LED+_LED+") (pintype "bidirectional"))
      (node (ref "CH3") (pin "P1") (pinfunction "1_P1") (pintype "passive"))
    )
    (net (code "75") (name "Net-(D2-C)") (class "Default")
      (node (ref "D2") (pin "A") (pinfunction "C_A") (pintype "passive"))
      (node (ref "J3") (pin "2") (pinfunction "2_2") (pintype "passive"))
      (node (ref "T1") (pin "2") (pinfunction "D_2") (pintype "passive"))
      (node (ref "T1") (pin "4") (pinfunction "D_4") (pintype "passive"))
    )
    (net (code "76") (name "Net-(D3-C)") (class "Default")
      (node (ref "D3") (pin "A") (pinfunction "C_A") (pintype "passive"))
      (node (ref "J4") (pin "2") (pinfunction "2_2") (pintype "passive"))
      (node (ref "T2") (pin "2") (pinfunction "D_2") (pintype "passive"))
      (node (ref "T2") (pin "4") (pinfunction "D_4") (pintype "passive"))
    )
    (net (code "77") (name "Net-(IC2A-+IN)") (class "Default")
      (node (ref "IC2") (pin "3") (pinfunction "+IN_3") (pintype "input"))
      (node (ref "R23") (pin "2") (pinfunction "2_2") (pintype "passive"))
      (node (ref "R24") (pin "1") (pinfunction "1_1") (pintype "passive"))
    )
    (net (code "78") (name "Net-(IC2A-OUT)") (class "Default")
      (node (ref "IC2") (pin "1") (pinfunction "OUT_1") (pintype "output"))
      (node (ref "R22") (pin "2") (pinfunction "2_2") (pintype "passive"))
    )
    (net (code "79") (name "Net-(IC2B-+IN)") (class "Default")
      (node (ref "IC2") (pin "5") (pinfunction "+IN_5") (pintype "input"))
      (node (ref "R26") (pin "2") (pinfunction "2_2") (pintype "passive"))
      (node (ref "R27") (pin "1") (pinfunction "1_1") (pintype "passive"))
    )
    (net (code "80") (name "Net-(IC2B-OUT)") (class "Default")
      (node (ref "IC2") (pin "7") (pinfunction "OUT_7") (pintype "output"))
      (node (ref "R29") (pin "2") (pinfunction "2_2") (pintype "passive"))
    )
    (net (code "81") (name "Net-(IC4A-I)") (class "Default")
      (node (ref "C9") (pin "1") (pinfunction "1_1") (pintype "passive"))
      (node (ref "IC4") (pin "1") (pinfunction "I_1") (pintype "input"))
      (node (ref "R29") (pin "1") (pinfunction "1_1") (pintype "passive"))
    )
    (net (code "82") (name "Net-(IC4B-I)") (class "Default")
      (node (ref "C8") (pin "1") (pinfunction "1_1") (pintype "passive"))
      (node (ref "IC4") (pin "3") (pinfunction "I_3") (pintype "input"))
      (node (ref "R22") (pin "1") (pinfunction "1_1") (pintype "passive"))
    )
    (net (code "83") (name "Net-(OK2-A)") (class "Default")
      (node (ref "OK2") (pin "1") (pinfunction "A_1") (pintype "passive"))
      (node (ref "R19") (pin "2") (pinfunction "2_2") (pintype "passive"))
    )
    (net (code "84") (name "Net-(OK3-A)") (class "Default")
      (node (ref "OK3") (pin "1") (pinfunction "A_1") (pintype "passive"))
      (node (ref "R8") (pin "2") (pinfunction "2_2") (pintype "passive"))
    )
    (net (code "85") (name "Net-(POWER_LED-PadA)") (class "Default")
      (node (ref "POWER_LED") (pin "A") (pinfunction "A_A") (pintype "passive"))
      (node (ref "R7") (pin "1") (pinfunction "1_1") (pintype "passive"))
    )
    (net (code "86") (name "Net-(Q1-D)") (class "Default")
      (node (ref "Q1") (pin "3") (pinfunction "D_3") (pintype "passive"))
      (node (ref "R17") (pin "1") (pinfunction "1_1") (pintype "passive"))
      (node (ref "R18") (pin "2") (pinfunction "2_2") (pintype "passive"))
    )
    (net (code "87") (name "Net-(Q1-S)") (class "Default")
      (node (ref "Q1") (pin "2") (pinfunction "S_2") (pintype "passive"))
      (node (ref "R21") (pin "A") (pinfunction "A_A") (pintype "passive"))
    )
    (net (code "88") (name "Net-(Q2-PadB)") (class "Default")
      (node (ref "Q2") (pin "B") (pinfunction "B_B") (pintype "passive"))
      (node (ref "R18") (pin "1") (pinfunction "1_1") (pintype "passive"))
    )
    (net (code "89") (name "Net-(Q2-PadC)") (class "Default")
      (node (ref "Q2") (pin "C") (pinfunction "C_C") (pintype "passive"))
      (node (ref "R19") (pin "1") (pinfunction "1_1") (pintype "passive"))
    )
    (net (code "90") (name "Net-(Q3-D)") (class "Default")
      (node (ref "Q3") (pin "3") (pinfunction "D_3") (pintype "passive"))
      (node (ref "R5") (pin "1") (pinfunction "1_1") (pintype "passive"))
      (node (ref "R6") (pin "2") (pinfunction "2_2") (pintype "passive"))
    )
    (net (code "91") (name "Net-(Q3-S)") (class "Default")
      (node (ref "Q3") (pin "2") (pinfunction "S_2") (pintype "passive"))
      (node (ref "R16") (pin "A") (pinfunction "A_A") (pintype "passive"))
    )
    (net (code "92") (name "Net-(Q4-PadB)") (class "Default")
      (node (ref "Q4") (pin "B") (pinfunction "B_B") (pintype "passive"))
      (node (ref "R6") (pin "1") (pinfunction "1_1") (pintype "passive"))
    )
    (net (code "93") (name "Net-(Q4-PadC)") (class "Default")
      (node (ref "Q4") (pin "C") (pinfunction "C_C") (pintype "passive"))
      (node (ref "R8") (pin "1") (pinfunction "1_1") (pintype "passive"))
    )
    (net (code "94") (name "Net-(Q5-PadB)") (class "Default")
      (node (ref "Q5") (pin "B") (pinfunction "B_B") (pintype "passive"))
      (node (ref "R13") (pin "2") (pinfunction "2_2") (pintype "passive"))
      (node (ref "R14") (pin "1") (pinfunction "1_1") (pintype "passive"))
    )
    (net (code "95") (name "Net-(Q6-PadC)") (class "Default")
      (node (ref "Q6") (pin "C") (pinfunction "C_C") (pintype "passive"))
      (node (ref "R14") (pin "2") (pinfunction "2_2") (pintype "passive"))
    )
    (net (code "96") (name "Net-(Q7-PadB)") (class "Default")
      (node (ref "Q7") (pin "B") (pinfunction "B_B") (pintype "passive"))
      (node (ref "R11") (pin "2") (pinfunction "2_2") (pintype "passive"))
      (node (ref "R12") (pin "1") (pinfunction "1_1") (pintype "passive"))
    )
    (net (code "97") (name "Net-(Q8-PadC)") (class "Default")
      (node (ref "Q8") (pin "C") (pinfunction "C_C") (pintype "passive"))
      (node (ref "R12") (pin "2") (pinfunction "2_2") (pintype "passive"))
    )
    (net (code "98") (name "Net-(Q9-PadB)") (class "Default")
      (node (ref "Q9") (pin "B") (pinfunction "B_B") (pintype "passive"))
      (node (ref "R10") (pin "1") (pinfunction "1_1") (pintype "passive"))
      (node (ref "R9") (pin "2") (pinfunction "2_2") (pintype "passive"))
    )
    (net (code "99") (name "Net-(Q10-PadC)") (class "Default")
      (node (ref "Q10") (pin "C") (pinfunction "C_C") (pintype "passive"))
      (node (ref "R10") (pin "2") (pinfunction "2_2") (pintype "passive"))
    )
    (net (code "100") (name "Net-(S1A-P)") (class "Default")
      (node (ref "JP10") (pin "PWR") (pinfunction "PWR_PWR") (pintype "bidirectional"))
      (node (ref "S1") (pin "2") (pinfunction "P_2") (pintype "passive"))
    )
    (net (code "101") (name "Net-(T2-G)") (class "Default")
      (node (ref "R2") (pin "2") (pinfunction "2_2") (pintype "passive"))
      (node (ref "T2") (pin "1") (pinfunction "G_1") (pintype "passive"))
    )
    (net (code "102") (name "VCC") (class "Default")
      (node (ref "C6") (pin "1") (pinfunction "1_1") (pintype "passive"))
      (node (ref "D2") (pin "C") (pinfunction "A_C") (pintype "passive"))
      (node (ref "D3") (pin "C") (pinfunction "A_C") (pintype "passive"))
      (node (ref "J3") (pin "1") (pinfunction "1_1") (pintype "passive"))
      (node (ref "J4") (pin "1") (pinfunction "1_1") (pintype "passive"))
      (node (ref "R7") (pin "2") (pinfunction "2_2") (pintype "passive"))
      (node (ref "TP2") (pin "TP") (pinfunction "TP_TP") (pintype "input"))
      (node (ref "U$3") (pin "3") (pinfunction "VO_3") (pintype "passive"))
    )
    (net (code "103") (name "VIN") (class "Default")
      (node (ref "D1") (pin "A") (pinfunction "A_A") (pintype "passive"))
      (node (ref "S1") (pin "1") (pinfunction "O_1") (pintype "passive"))
    )
    (net (code "104") (name "unconnected-(OK2-BAS-Pad6)") (class "Default")
      (node (ref "OK2") (pin "6") (pinfunction "BAS_6") (pintype "passive"))
    )
    (net (code "105") (name "unconnected-(OK3-BAS-Pad6)") (class "Default")
      (node (ref "OK3") (pin "6") (pinfunction "BAS_6") (pintype "passive"))
    )
    (net (code "106") (name "unconnected-(S1A-S-Pad3)") (class "Default")
      (node (ref "S1") (pin "3") (pinfunction "S_3") (pintype "passive"))
    )
  )
)
